# obc_flash.net
KiCad netlist of a schematic drawn in Altium Designer
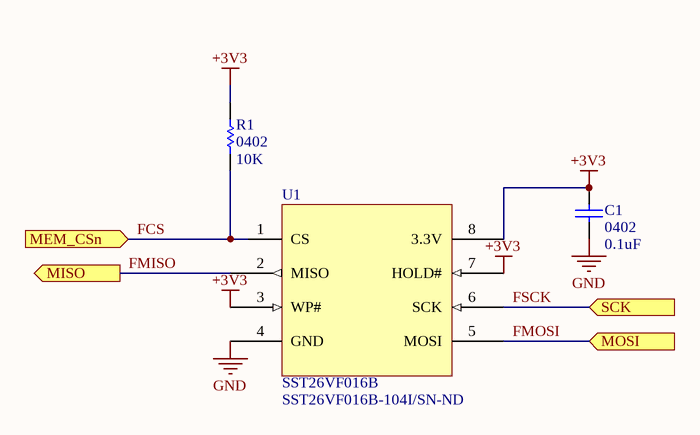
[diagram p0: obc_flash.SchDoc]

(export (version "E")
  (design (tool "Eeschema 10.0.6"))
  (components
    (comp (ref "C1")
      (value "0402")
      (footprint "CAP0402R")
      (description "0402 capacitor")
      (fields (field (name "ALTIUM_VALUE") "0.1uF"))
      (libsource (lib "heron-general") (part "CAP0402"))
    )
    (comp (ref "R1")
      (value "0402")
      (footprint "RES0402R")
      (description "0402 resistor")
      (fields (field (name "ALTIUM_VALUE") "10K"))
      (libsource (lib "heron-general") (part "RES0402"))
    )
    (comp (ref "U1")
      (value "SST26VF016B")
      (footprint "SOIC127P500X600-8N")
      (description "2.5V/3.0V 16 Mbit Serial Quad I/O (SQI) Flash Memory")
      (fields (field (name "SUPPLIER PART NUMBER 1") "SST26VF016B-104I/SN-ND"))
      (libsource (lib "heron-general") (part "SST26VF016B"))
    )
  )
  (nets
    (net (code "1") (name "+3V3") (class "Default")
      (node (ref "C1") (pin "1") (pinfunction "1_1") (pintype "passive"))
      (node (ref "R1") (pin "2") (pinfunction "2_2") (pintype "passive"))
      (node (ref "U1") (pin "3") (pinfunction "WP#_3") (pintype "input"))
      (node (ref "U1") (pin "7") (pinfunction "HOLD#_7") (pintype "input"))
      (node (ref "U1") (pin "8") (pinfunction "3.3V_8") (pintype "power_in"))
    )
    (net (code "2") (name "/FCS") (class "Default")
      (node (ref "R1") (pin "1") (pinfunction "1_1") (pintype "passive"))
      (node (ref "U1") (pin "1") (pinfunction "CS_1") (pintype "passive"))
    )
    (net (code "3") (name "/FMISO") (class "Default")
      (node (ref "U1") (pin "2") (pinfunction "MISO_2") (pintype "output"))
    )
    (net (code "4") (name "/FMOSI") (class "Default")
      (node (ref "U1") (pin "5") (pinfunction "MOSI_5") (pintype "passive"))
    )
    (net (code "5") (name "/FSCK") (class "Default")
      (node (ref "U1") (pin "6") (pinfunction "SCK_6") (pintype "input"))
    )
    (net (code "6") (name "GND") (class "Default")
      (node (ref "C1") (pin "2") (pinfunction "2_2") (pintype "passive"))
      (node (ref "U1") (pin "4") (pinfunction "GND_4") (pintype "power_in"))
    )
  )
)
